# ProPrj___2025-12-14-16-16-23.net
KiCad netlist of a schematic drawn in EasyEDA Pro
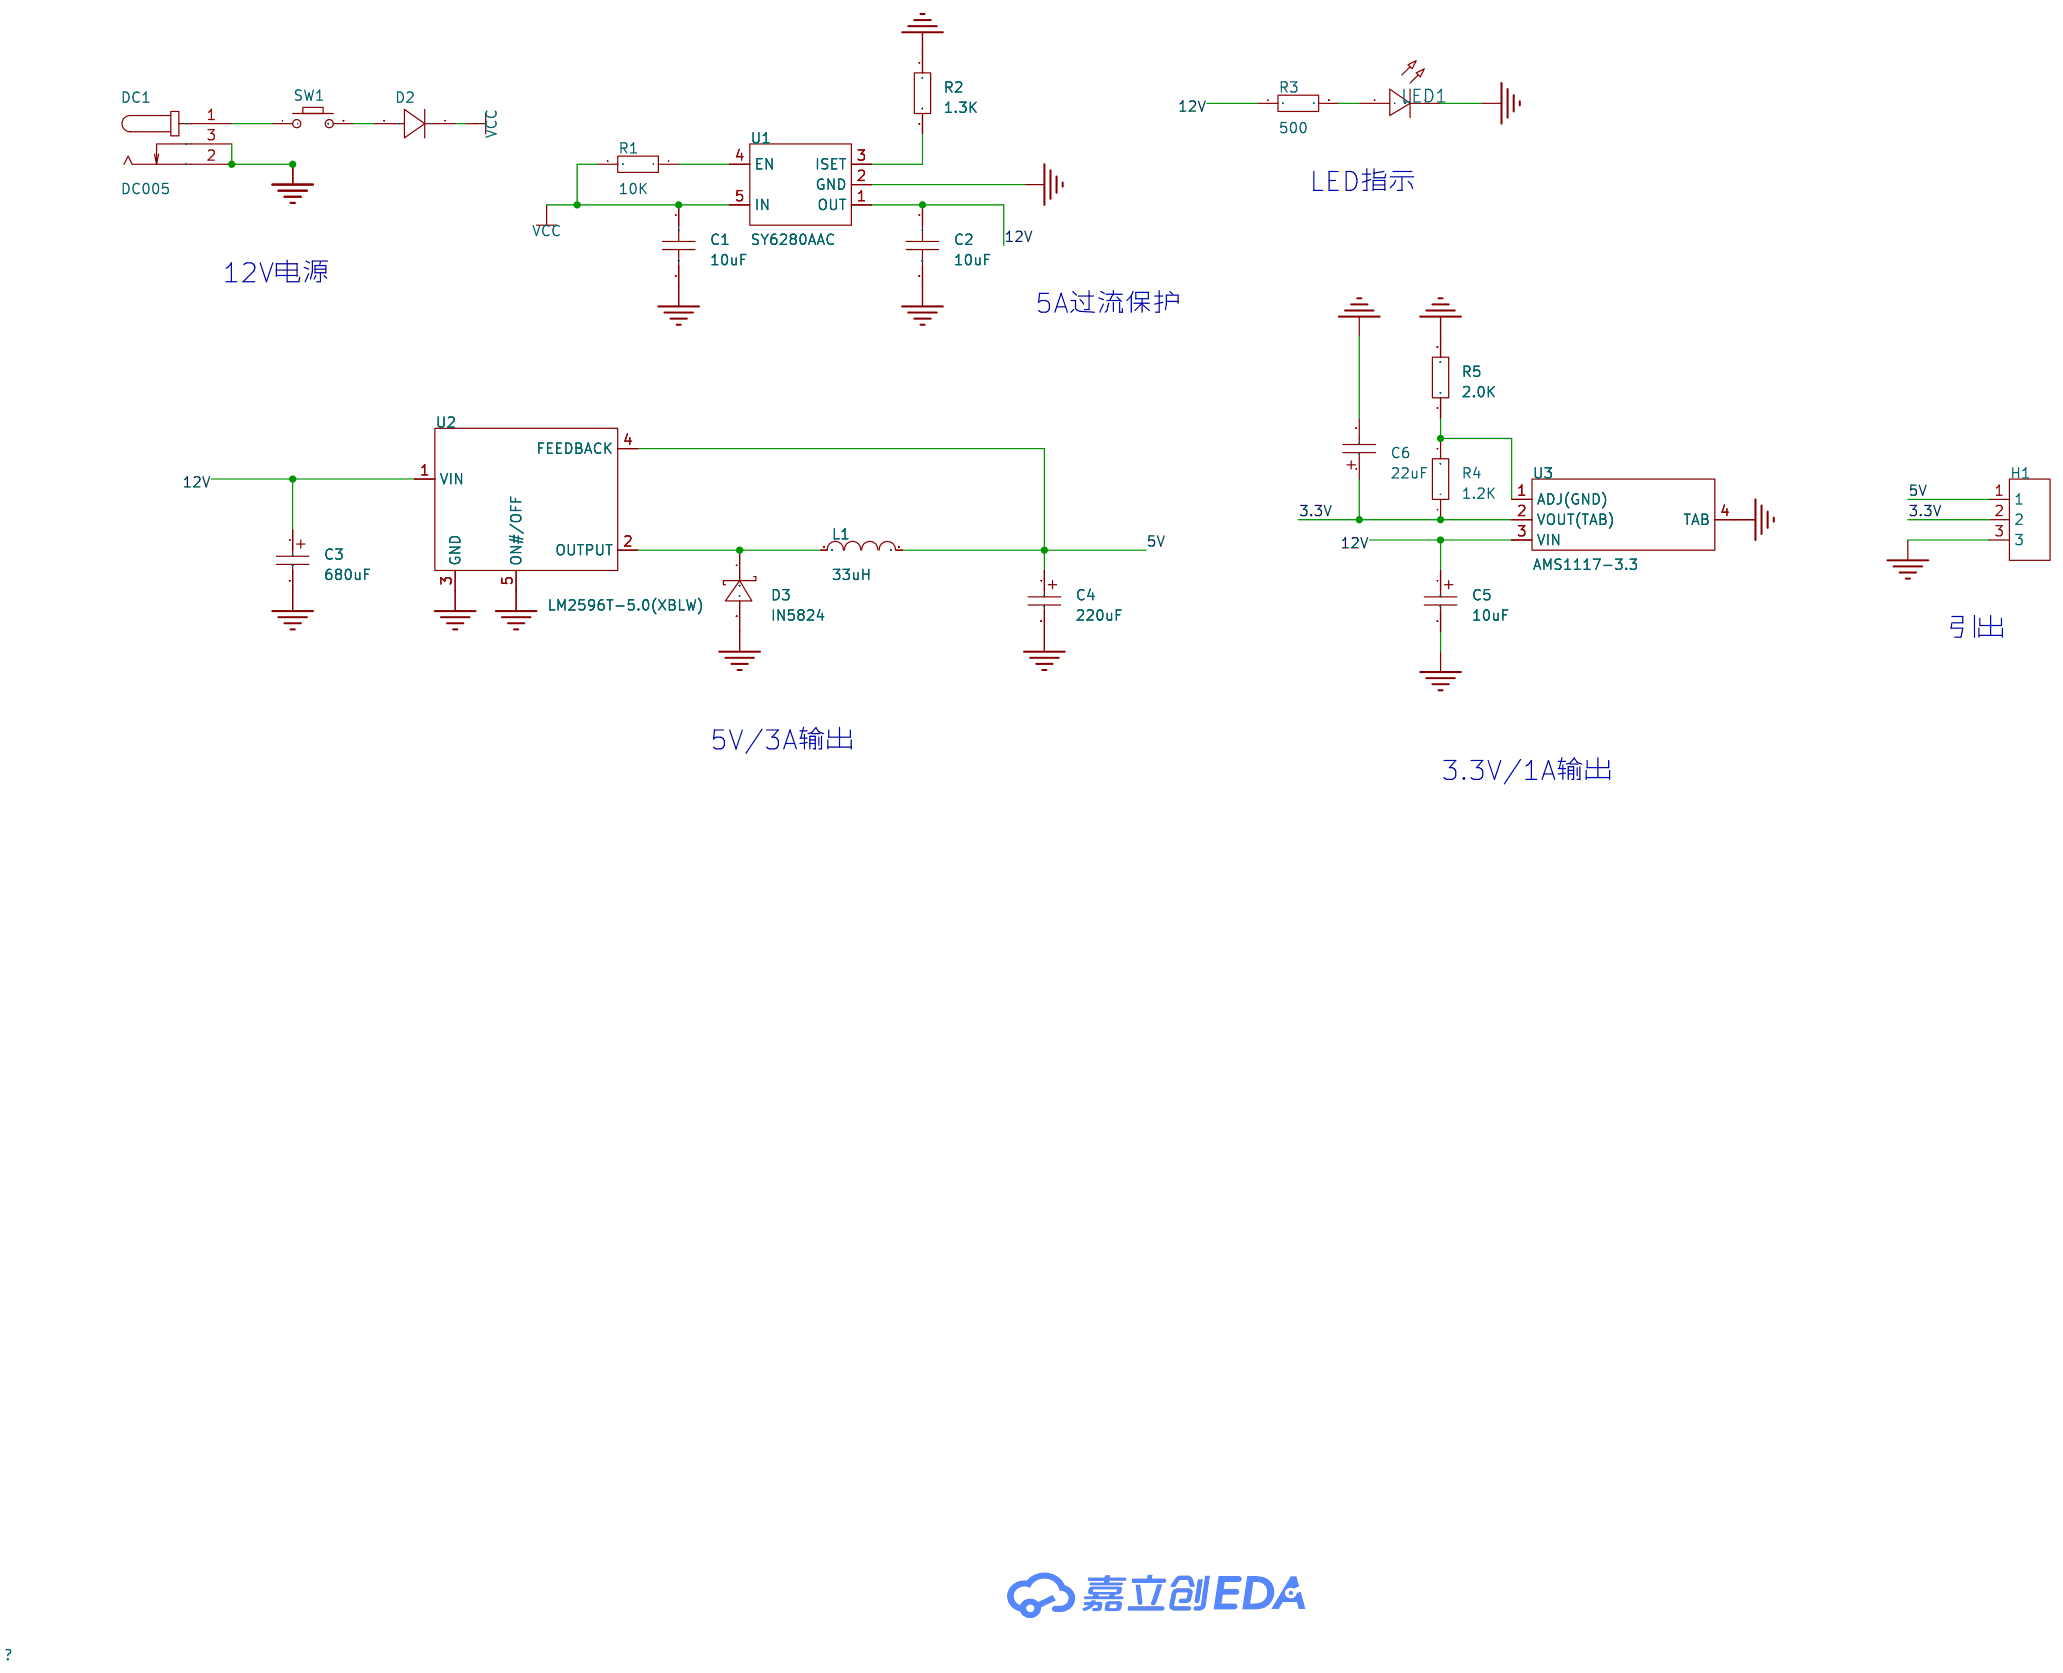
[diagram p0: schematic sheet]

(export (version "E")
  (design (tool "Eeschema 10.0.6"))
  (components
    (comp (ref "C1")
      (value "10uF")
      (footprint "easyedapro:C0603")
      (libsource (lib "easyedapro") (part "Capacitance"))
    )
    (comp (ref "C2")
      (value "10uF")
      (footprint "easyedapro:C0603")
      (libsource (lib "easyedapro") (part "Capacitance"))
    )
    (comp (ref "C3")
      (value "680uF")
      (footprint "easyedapro:C_Ele_SMD_3x5.4mm")
      (libsource (lib "easyedapro") (part "CAP"))
    )
    (comp (ref "C4")
      (value "220uF")
      (footprint "easyedapro:C_Ele_SMD_3x5.4mm")
      (libsource (lib "easyedapro") (part "CAP"))
    )
    (comp (ref "C5")
      (value "10uF")
      (footprint "easyedapro:C_Ele_SMD_3x5.4mm")
      (libsource (lib "easyedapro") (part "CAP"))
    )
    (comp (ref "C6")
      (value "22uF")
      (footprint "easyedapro:C_Ele_SMD_3x5.4mm")
      (libsource (lib "easyedapro") (part "CAP"))
    )
    (comp (ref "D2")
      (value "~")
      (footprint "easyedapro:DO_1N4007")
      (libsource (lib "easyedapro") (part "D_1N4007"))
    )
    (comp (ref "D3")
      (value "IN5824")
      (footprint "easyedapro:SMAF_L3.5-W2.6-LS4.7-RD")
      (libsource (lib "easyedapro") (part "IN5824"))
    )
    (comp (ref "DC1")
      (value "DC005")
      (footprint "easyedapro:DC-IN-TH_DC005")
      (description "连接器类型:DC电源插座;安装方式:弯插;触点内径:2mm;触点外径:6.3mm;额定电流:500mA;额定电压:12V;工作温度:-30°C~+70°C;")
      (fields (field (name "Manufacturer") "SHOU HAN(首韩)"))
      (libsource (lib "easyedapro") (part "DC005_C431533"))
    )
    (comp (ref "H1")
      (value "~")
      (footprint "easyedapro:HDR-TH_3P-P2.54-V-F")
      (libsource (lib "easyedapro") (part "PM254V-11-03-H85"))
    )
    (comp (ref "L1")
      (value "33uH")
      (footprint "easyedapro:L0603")
      (libsource (lib "easyedapro") (part "SDFL1608S100KTF"))
    )
    (comp (ref "LED1")
      (value "~")
      (footprint "easyedapro:LED_0603")
      (libsource (lib "easyedapro") (part "LED_R"))
    )
    (comp (ref "R1") (value "10K") (footprint "easyedapro:R0603") (libsource (lib "easyedapro") (part "电阻")))
    (comp (ref "R2") (value "1.3K") (footprint "easyedapro:R0603") (libsource (lib "easyedapro") (part "电阻")))
    (comp (ref "R3") (value "500") (footprint "easyedapro:R0603") (libsource (lib "easyedapro") (part "电阻")))
    (comp (ref "R4") (value "1.2K") (footprint "easyedapro:R0603") (libsource (lib "easyedapro") (part "电阻")))
    (comp (ref "R5") (value "2.0K") (footprint "easyedapro:R0603") (libsource (lib "easyedapro") (part "电阻")))
    (comp (ref "SW1")
      (value "~")
      (footprint "easyedapro:Key_TH_3.5x6x4.3")
      (libsource (lib "easyedapro") (part "Key_TH_3.5x6x4.3"))
    )
    (comp (ref "U1")
      (value "SY6280AAC")
      (footprint "easyedapro:SOT-23-5_L3.0-W1.7-P0.95-LS2.8-BR")
      (libsource (lib "easyedapro") (part "SY6280AAC_C9900003867"))
    )
    (comp (ref "U2")
      (value "LM2596T-5.0(XBLW)")
      (footprint "easyedapro:TO-220-5L_L10.2-W4.5-P1.71-L")
      (description "功能类型:降压型;工作电压:6V~40V;输出电压:5V;输出电流:3A;输出类型:固定;")
      (fields (field (name "Manufacturer") "XBLW(芯伯乐)"))
      (libsource (lib "easyedapro") (part "LM2596T-5.0(XBLW)"))
    )
    (comp (ref "U3")
      (value "AMS1117-3.3")
      (footprint "easyedapro:SOT-223-4_L6.5-W3.5-P2.30-LS7.0-BR")
      (description "输出类型:固定;工作电压:12V;输出电压:3.3V;输出电流:1A;电源纹波抑制比(PSRR):60dB@(120Hz);输出极性:正极;")
      (fields (field (name "Manufacturer") "UMW(友台半导体)"))
      (libsource (lib "easyedapro") (part "AMS1117-3.3_C347222"))
    )
  )
  (nets
    (net (code "1") (name "/3.3V") (class "Default")
      (node (ref "C6") (pin "1") (pinfunction "1_1") (pintype "input"))
      (node (ref "H1") (pin "2") (pinfunction "2_2") (pintype "unspecified"))
      (node (ref "R4") (pin "1") (pinfunction "1_1") (pintype "input"))
      (node (ref "U3") (pin "2") (pinfunction "VOUT(TAB)_2") (pintype "unspecified"))
    )
    (net (code "2") (name "/5V") (class "Default")
      (node (ref "C4") (pin "1") (pinfunction "1_1") (pintype "input"))
      (node (ref "H1") (pin "1") (pinfunction "1_1") (pintype "unspecified"))
      (node (ref "L1") (pin "2") (pinfunction "2_2") (pintype "unspecified"))
      (node (ref "U2") (pin "4") (pinfunction "FEEDBACK_4") (pintype "unspecified"))
    )
    (net (code "3") (name "/12V") (class "Default")
      (node (ref "C2") (pin "1") (pinfunction "1_1") (pintype "input"))
      (node (ref "C3") (pin "1") (pinfunction "1_1") (pintype "input"))
      (node (ref "C5") (pin "1") (pinfunction "1_1") (pintype "input"))
      (node (ref "R3") (pin "1") (pinfunction "1_1") (pintype "input"))
      (node (ref "U1") (pin "1") (pinfunction "OUT_1") (pintype "unspecified"))
      (node (ref "U2") (pin "1") (pinfunction "VIN_1") (pintype "unspecified"))
      (node (ref "U3") (pin "3") (pinfunction "VIN_3") (pintype "unspecified"))
    )
    (net (code "4") (name "GND") (class "Default")
      (node (ref "C1") (pin "2") (pinfunction "2_2") (pintype "input"))
      (node (ref "C2") (pin "2") (pinfunction "2_2") (pintype "input"))
      (node (ref "C3") (pin "2") (pinfunction "2_2") (pintype "input"))
      (node (ref "C4") (pin "2") (pinfunction "2_2") (pintype "input"))
      (node (ref "C5") (pin "2") (pinfunction "2_2") (pintype "input"))
      (node (ref "C6") (pin "2") (pinfunction "2_2") (pintype "input"))
      (node (ref "D3") (pin "2") (pinfunction "A_2") (pintype "unspecified"))
      (node (ref "DC1") (pin "2") (pinfunction "2_2") (pintype "unspecified"))
      (node (ref "DC1") (pin "3") (pinfunction "3_3") (pintype "unspecified"))
      (node (ref "H1") (pin "3") (pinfunction "3_3") (pintype "unspecified"))
      (node (ref "LED1") (pin "1") (pinfunction "C_1") (pintype "input"))
      (node (ref "R2") (pin "1") (pinfunction "1_1") (pintype "input"))
      (node (ref "R5") (pin "2") (pinfunction "2_2") (pintype "input"))
      (node (ref "U1") (pin "2") (pinfunction "GND_2") (pintype "unspecified"))
      (node (ref "U2") (pin "3") (pinfunction "GND_3") (pintype "unspecified"))
      (node (ref "U2") (pin "5") (pinfunction "ON#/OFF_5") (pintype "unspecified"))
      (node (ref "U3") (pin "4") (pinfunction "TAB_4") (pintype "unspecified"))
    )
    (net (code "5") (name "Net-(D2-A)") (class "Default")
      (node (ref "D2") (pin "2") (pinfunction "A_2") (pintype "input"))
      (node (ref "SW1") (pin "B") (pinfunction "B_B") (pintype "input"))
    )
    (net (code "6") (name "Net-(D3-C)") (class "Default")
      (node (ref "D3") (pin "1") (pinfunction "C_1") (pintype "unspecified"))
      (node (ref "L1") (pin "1") (pinfunction "1_1") (pintype "unspecified"))
      (node (ref "U2") (pin "2") (pinfunction "OUTPUT_2") (pintype "unspecified"))
    )
    (net (code "7") (name "Net-(DC1-Pad1)") (class "Default")
      (node (ref "DC1") (pin "1") (pinfunction "1_1") (pintype "unspecified"))
      (node (ref "SW1") (pin "A") (pinfunction "A_A") (pintype "input"))
    )
    (net (code "8") (name "Net-(LED1-A)") (class "Default")
      (node (ref "LED1") (pin "2") (pinfunction "A_2") (pintype "input"))
      (node (ref "R3") (pin "2") (pinfunction "2_2") (pintype "input"))
    )
    (net (code "9") (name "Net-(U1-EN)") (class "Default")
      (node (ref "R1") (pin "1") (pinfunction "1_1") (pintype "input"))
      (node (ref "U1") (pin "4") (pinfunction "EN_4") (pintype "unspecified"))
    )
    (net (code "10") (name "Net-(U1-ISET)") (class "Default")
      (node (ref "R2") (pin "2") (pinfunction "2_2") (pintype "input"))
      (node (ref "U1") (pin "3") (pinfunction "ISET_3") (pintype "unspecified"))
    )
    (net (code "11") (name "Net-(U3-ADJ(GND))") (class "Default")
      (node (ref "R4") (pin "2") (pinfunction "2_2") (pintype "input"))
      (node (ref "R5") (pin "1") (pinfunction "1_1") (pintype "input"))
      (node (ref "U3") (pin "1") (pinfunction "ADJ(GND)_1") (pintype "unspecified"))
    )
    (net (code "12") (name "VCC") (class "Default")
      (node (ref "C1") (pin "1") (pinfunction "1_1") (pintype "input"))
      (node (ref "D2") (pin "1") (pinfunction "K_1") (pintype "input"))
      (node (ref "R1") (pin "2") (pinfunction "2_2") (pintype "input"))
      (node (ref "U1") (pin "5") (pinfunction "IN_5") (pintype "unspecified"))
    )
  )
)
